# HID_Board.net
KiCad netlist of a schematic drawn in EAGLE
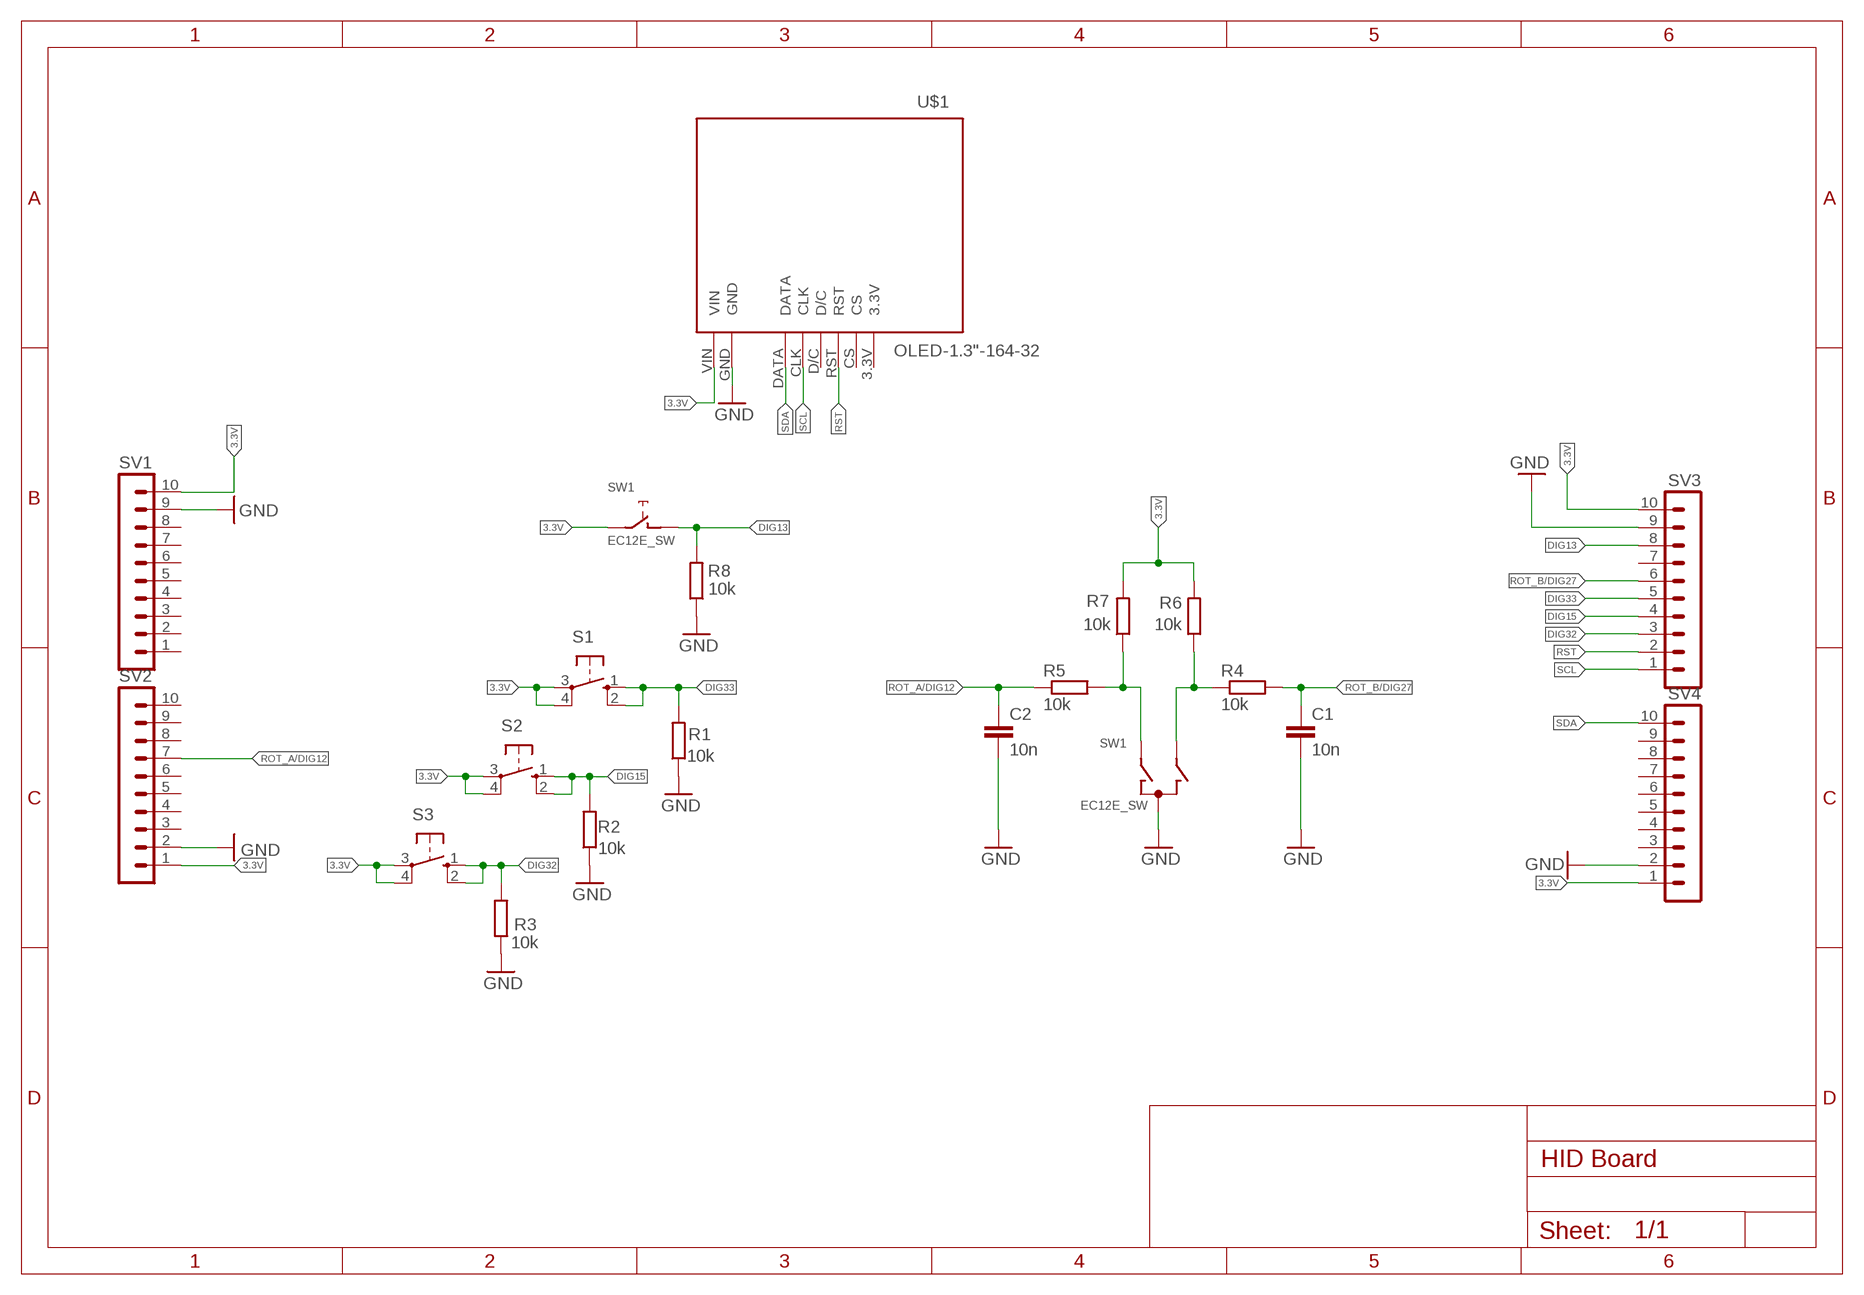
[diagram p0: schematic, sheet 1]

(export (version "E")
  (design (tool "Eeschema 10.0.6"))
  (components
    (comp (ref "C1")
      (value "10n")
      (footprint "eagle-import:C1206")
      (libsource (lib "eagle-import") (part "C-EUC1206"))
    )
    (comp (ref "C2")
      (value "10n")
      (footprint "eagle-import:C1206")
      (libsource (lib "eagle-import") (part "C-EUC1206"))
    )
    (comp (ref "R1")
      (value "10k")
      (footprint "eagle-import:M1206")
      (libsource (lib "eagle-import") (part "R-EU_M1206"))
    )
    (comp (ref "R2")
      (value "10k")
      (footprint "eagle-import:M1206")
      (libsource (lib "eagle-import") (part "R-EU_M1206"))
    )
    (comp (ref "R3")
      (value "10k")
      (footprint "eagle-import:M1206")
      (libsource (lib "eagle-import") (part "R-EU_M1206"))
    )
    (comp (ref "R4")
      (value "10k")
      (footprint "eagle-import:M1206")
      (libsource (lib "eagle-import") (part "R-EU_M1206"))
    )
    (comp (ref "R5")
      (value "10k")
      (footprint "eagle-import:M1206")
      (libsource (lib "eagle-import") (part "R-EU_M1206"))
    )
    (comp (ref "R6")
      (value "10k")
      (footprint "eagle-import:M1206")
      (libsource (lib "eagle-import") (part "R-EU_M1206"))
    )
    (comp (ref "R7")
      (value "10k")
      (footprint "eagle-import:M1206")
      (libsource (lib "eagle-import") (part "R-EU_M1206"))
    )
    (comp (ref "R8")
      (value "10k")
      (footprint "eagle-import:M1206")
      (libsource (lib "eagle-import") (part "R-EU_M1206"))
    )
    (comp (ref "S1")
      (value "10-XX")
      (footprint "eagle-import:B3F-10XX")
      (fields (field (name "MPN") "B3F-1000"))
      (libsource (lib "eagle-import") (part "10-XX"))
    )
    (comp (ref "S2")
      (value "10-XX")
      (footprint "eagle-import:B3F-10XX")
      (fields (field (name "MPN") "B3F-1000"))
      (libsource (lib "eagle-import") (part "10-XX"))
    )
    (comp (ref "S3")
      (value "10-XX")
      (footprint "eagle-import:B3F-10XX")
      (fields (field (name "MPN") "B3F-1000"))
      (libsource (lib "eagle-import") (part "10-XX"))
    )
    (comp (ref "SV1")
      (value "MA10-1")
      (footprint "eagle-import:MA10-1")
      (libsource (lib "eagle-import") (part "MA10-1"))
    )
    (comp (ref "SV2")
      (value "MA10-1")
      (footprint "eagle-import:MA10-1")
      (libsource (lib "eagle-import") (part "MA10-1"))
    )
    (comp (ref "SV3")
      (value "MA10-1")
      (footprint "eagle-import:MA10-1")
      (libsource (lib "eagle-import") (part "MA10-1"))
    )
    (comp (ref "SV4")
      (value "MA10-1")
      (footprint "eagle-import:MA10-1")
      (libsource (lib "eagle-import") (part "MA10-1"))
    )
    (comp (ref "SW1")
      (value "EC12E_SW")
      (footprint "eagle-import:ALPS_EC12E_SW")
      (fields (field (name "MPN") "EC12E2424407"))
      (libsource (lib "eagle-import") (part "EC12E_SW"))
    )
    (comp (ref "U$1")
      (value "OLED-1.3\"-164-32")
      (footprint "eagle-import:OLED-1.3_-164-32")
      (libsource (lib "eagle-import") (part "OLED-1.3{dblquote}-164-32"))
    )
  )
  (nets
    (net (code "1") (name "3.3V") (class "Default")
      (node (ref "R6") (pin "2") (pinfunction "2_2") (pintype "passive"))
      (node (ref "R7") (pin "2") (pinfunction "2_2") (pintype "passive"))
      (node (ref "S1") (pin "3") (pinfunction "P_3") (pintype "passive"))
      (node (ref "S1") (pin "4") (pinfunction "P1_4") (pintype "passive"))
      (node (ref "S2") (pin "3") (pinfunction "P_3") (pintype "passive"))
      (node (ref "S2") (pin "4") (pinfunction "P1_4") (pintype "passive"))
      (node (ref "S3") (pin "3") (pinfunction "P_3") (pintype "passive"))
      (node (ref "S3") (pin "4") (pinfunction "P1_4") (pintype "passive"))
      (node (ref "SV1") (pin "10") (pinfunction "10_10") (pintype "passive"))
      (node (ref "SV2") (pin "1") (pinfunction "1_1") (pintype "passive"))
      (node (ref "SV3") (pin "10") (pinfunction "10_10") (pintype "passive"))
      (node (ref "SV4") (pin "1") (pinfunction "1_1") (pintype "passive"))
      (node (ref "SW1") (pin "E") (pinfunction "2_E") (pintype "passive"))
      (node (ref "U$1") (pin "VIN") (pinfunction "VIN_VIN") (pintype "bidirectional"))
    )
    (net (code "2") (name "DIG13") (class "Default")
      (node (ref "R8") (pin "2") (pinfunction "2_2") (pintype "passive"))
      (node (ref "SV3") (pin "8") (pinfunction "8_8") (pintype "passive"))
      (node (ref "SW1") (pin "D") (pinfunction "1_D") (pintype "passive"))
    )
    (net (code "3") (name "DIG15") (class "Default")
      (node (ref "R2") (pin "2") (pinfunction "2_2") (pintype "passive"))
      (node (ref "S2") (pin "1") (pinfunction "S_1") (pintype "passive"))
      (node (ref "S2") (pin "2") (pinfunction "S1_2") (pintype "passive"))
      (node (ref "SV3") (pin "4") (pinfunction "4_4") (pintype "passive"))
    )
    (net (code "4") (name "DIG32") (class "Default")
      (node (ref "R3") (pin "2") (pinfunction "2_2") (pintype "passive"))
      (node (ref "S3") (pin "1") (pinfunction "S_1") (pintype "passive"))
      (node (ref "S3") (pin "2") (pinfunction "S1_2") (pintype "passive"))
      (node (ref "SV3") (pin "3") (pinfunction "3_3") (pintype "passive"))
    )
    (net (code "5") (name "DIG33") (class "Default")
      (node (ref "R1") (pin "2") (pinfunction "2_2") (pintype "passive"))
      (node (ref "S1") (pin "1") (pinfunction "S_1") (pintype "passive"))
      (node (ref "S1") (pin "2") (pinfunction "S1_2") (pintype "passive"))
      (node (ref "SV3") (pin "5") (pinfunction "5_5") (pintype "passive"))
    )
    (net (code "6") (name "GND") (class "Default")
      (node (ref "C1") (pin "2") (pinfunction "2_2") (pintype "passive"))
      (node (ref "C2") (pin "2") (pinfunction "2_2") (pintype "passive"))
      (node (ref "R1") (pin "1") (pinfunction "1_1") (pintype "passive"))
      (node (ref "R2") (pin "1") (pinfunction "1_1") (pintype "passive"))
      (node (ref "R3") (pin "1") (pinfunction "1_1") (pintype "passive"))
      (node (ref "R8") (pin "1") (pinfunction "1_1") (pintype "passive"))
      (node (ref "SV1") (pin "9") (pinfunction "9_9") (pintype "passive"))
      (node (ref "SV2") (pin "2") (pinfunction "2_2") (pintype "passive"))
      (node (ref "SV3") (pin "9") (pinfunction "9_9") (pintype "passive"))
      (node (ref "SV4") (pin "2") (pinfunction "2_2") (pintype "passive"))
      (node (ref "SW1") (pin "C") (pinfunction "C_C") (pintype "passive"))
      (node (ref "U$1") (pin "GND") (pinfunction "GND_GND") (pintype "bidirectional"))
    )
    (net (code "7") (name "Net-(R4-Pad1)") (class "Default")
      (node (ref "R4") (pin "1") (pinfunction "1_1") (pintype "passive"))
      (node (ref "R6") (pin "1") (pinfunction "1_1") (pintype "passive"))
      (node (ref "SW1") (pin "B") (pinfunction "B_B") (pintype "passive"))
    )
    (net (code "8") (name "Net-(R5-Pad2)") (class "Default")
      (node (ref "R5") (pin "2") (pinfunction "2_2") (pintype "passive"))
      (node (ref "R7") (pin "1") (pinfunction "1_1") (pintype "passive"))
      (node (ref "SW1") (pin "A") (pinfunction "A_A") (pintype "passive"))
    )
    (net (code "9") (name "ROT_A{slash}DIG12") (class "Default")
      (node (ref "C2") (pin "1") (pinfunction "1_1") (pintype "passive"))
      (node (ref "R5") (pin "1") (pinfunction "1_1") (pintype "passive"))
      (node (ref "SV2") (pin "7") (pinfunction "7_7") (pintype "passive"))
    )
    (net (code "10") (name "ROT_B{slash}DIG27") (class "Default")
      (node (ref "C1") (pin "1") (pinfunction "1_1") (pintype "passive"))
      (node (ref "R4") (pin "2") (pinfunction "2_2") (pintype "passive"))
      (node (ref "SV3") (pin "6") (pinfunction "6_6") (pintype "passive"))
    )
    (net (code "11") (name "RST") (class "Default")
      (node (ref "SV3") (pin "2") (pinfunction "2_2") (pintype "passive"))
      (node (ref "U$1") (pin "RST") (pinfunction "RST_RST") (pintype "bidirectional"))
    )
    (net (code "12") (name "SCL") (class "Default")
      (node (ref "SV3") (pin "1") (pinfunction "1_1") (pintype "passive"))
      (node (ref "U$1") (pin "CLK") (pinfunction "CLK_CLK") (pintype "bidirectional"))
    )
    (net (code "13") (name "SDA") (class "Default")
      (node (ref "SV4") (pin "10") (pinfunction "10_10") (pintype "passive"))
      (node (ref "U$1") (pin "DATA") (pinfunction "DATA_DATA") (pintype "bidirectional"))
    )
    (net (code "14") (name "unconnected-(SV1-Pad1)") (class "Default")
      (node (ref "SV1") (pin "1") (pinfunction "1_1") (pintype "passive"))
    )
    (net (code "15") (name "unconnected-(SV1-Pad2)") (class "Default")
      (node (ref "SV1") (pin "2") (pinfunction "2_2") (pintype "passive"))
    )
    (net (code "16") (name "unconnected-(SV1-Pad3)") (class "Default")
      (node (ref "SV1") (pin "3") (pinfunction "3_3") (pintype "passive"))
    )
    (net (code "17") (name "unconnected-(SV1-Pad4)") (class "Default")
      (node (ref "SV1") (pin "4") (pinfunction "4_4") (pintype "passive"))
    )
    (net (code "18") (name "unconnected-(SV1-Pad5)") (class "Default")
      (node (ref "SV1") (pin "5") (pinfunction "5_5") (pintype "passive"))
    )
    (net (code "19") (name "unconnected-(SV1-Pad6)") (class "Default")
      (node (ref "SV1") (pin "6") (pinfunction "6_6") (pintype "passive"))
    )
    (net (code "20") (name "unconnected-(SV1-Pad7)") (class "Default")
      (node (ref "SV1") (pin "7") (pinfunction "7_7") (pintype "passive"))
    )
    (net (code "21") (name "unconnected-(SV1-Pad8)") (class "Default")
      (node (ref "SV1") (pin "8") (pinfunction "8_8") (pintype "passive"))
    )
    (net (code "22") (name "unconnected-(SV2-Pad3)") (class "Default")
      (node (ref "SV2") (pin "3") (pinfunction "3_3") (pintype "passive"))
    )
    (net (code "23") (name "unconnected-(SV2-Pad4)") (class "Default")
      (node (ref "SV2") (pin "4") (pinfunction "4_4") (pintype "passive"))
    )
    (net (code "24") (name "unconnected-(SV2-Pad5)") (class "Default")
      (node (ref "SV2") (pin "5") (pinfunction "5_5") (pintype "passive"))
    )
    (net (code "25") (name "unconnected-(SV2-Pad6)") (class "Default")
      (node (ref "SV2") (pin "6") (pinfunction "6_6") (pintype "passive"))
    )
    (net (code "26") (name "unconnected-(SV2-Pad8)") (class "Default")
      (node (ref "SV2") (pin "8") (pinfunction "8_8") (pintype "passive"))
    )
    (net (code "27") (name "unconnected-(SV2-Pad9)") (class "Default")
      (node (ref "SV2") (pin "9") (pinfunction "9_9") (pintype "passive"))
    )
    (net (code "28") (name "unconnected-(SV2-Pad10)") (class "Default")
      (node (ref "SV2") (pin "10") (pinfunction "10_10") (pintype "passive"))
    )
    (net (code "29") (name "unconnected-(SV3-Pad7)") (class "Default")
      (node (ref "SV3") (pin "7") (pinfunction "7_7") (pintype "passive"))
    )
    (net (code "30") (name "unconnected-(SV4-Pad3)") (class "Default")
      (node (ref "SV4") (pin "3") (pinfunction "3_3") (pintype "passive"))
    )
    (net (code "31") (name "unconnected-(SV4-Pad4)") (class "Default")
      (node (ref "SV4") (pin "4") (pinfunction "4_4") (pintype "passive"))
    )
    (net (code "32") (name "unconnected-(SV4-Pad5)") (class "Default")
      (node (ref "SV4") (pin "5") (pinfunction "5_5") (pintype "passive"))
    )
    (net (code "33") (name "unconnected-(SV4-Pad6)") (class "Default")
      (node (ref "SV4") (pin "6") (pinfunction "6_6") (pintype "passive"))
    )
    (net (code "34") (name "unconnected-(SV4-Pad7)") (class "Default")
      (node (ref "SV4") (pin "7") (pinfunction "7_7") (pintype "passive"))
    )
    (net (code "35") (name "unconnected-(SV4-Pad8)") (class "Default")
      (node (ref "SV4") (pin "8") (pinfunction "8_8") (pintype "passive"))
    )
    (net (code "36") (name "unconnected-(SV4-Pad9)") (class "Default")
      (node (ref "SV4") (pin "9") (pinfunction "9_9") (pintype "passive"))
    )
    (net (code "37") (name "unconnected-(U$1-Pad3.3V)") (class "Default")
      (node (ref "U$1") (pin "3.3V") (pinfunction "3.3V_3.3V") (pintype "bidirectional"))
    )
    (net (code "38") (name "unconnected-(U$1-PadCS)") (class "Default")
      (node (ref "U$1") (pin "CS") (pinfunction "CS_CS") (pintype "bidirectional"))
    )
    (net (code "39") (name "unconnected-(U$1-PadD{slash}C)") (class "Default")
      (node (ref "U$1") (pin "D/C") (pinfunction "D/C_D/C") (pintype "bidirectional"))
    )
  )
)
